# Source.net
KiCad netlist of a schematic drawn in EasyEDA Pro
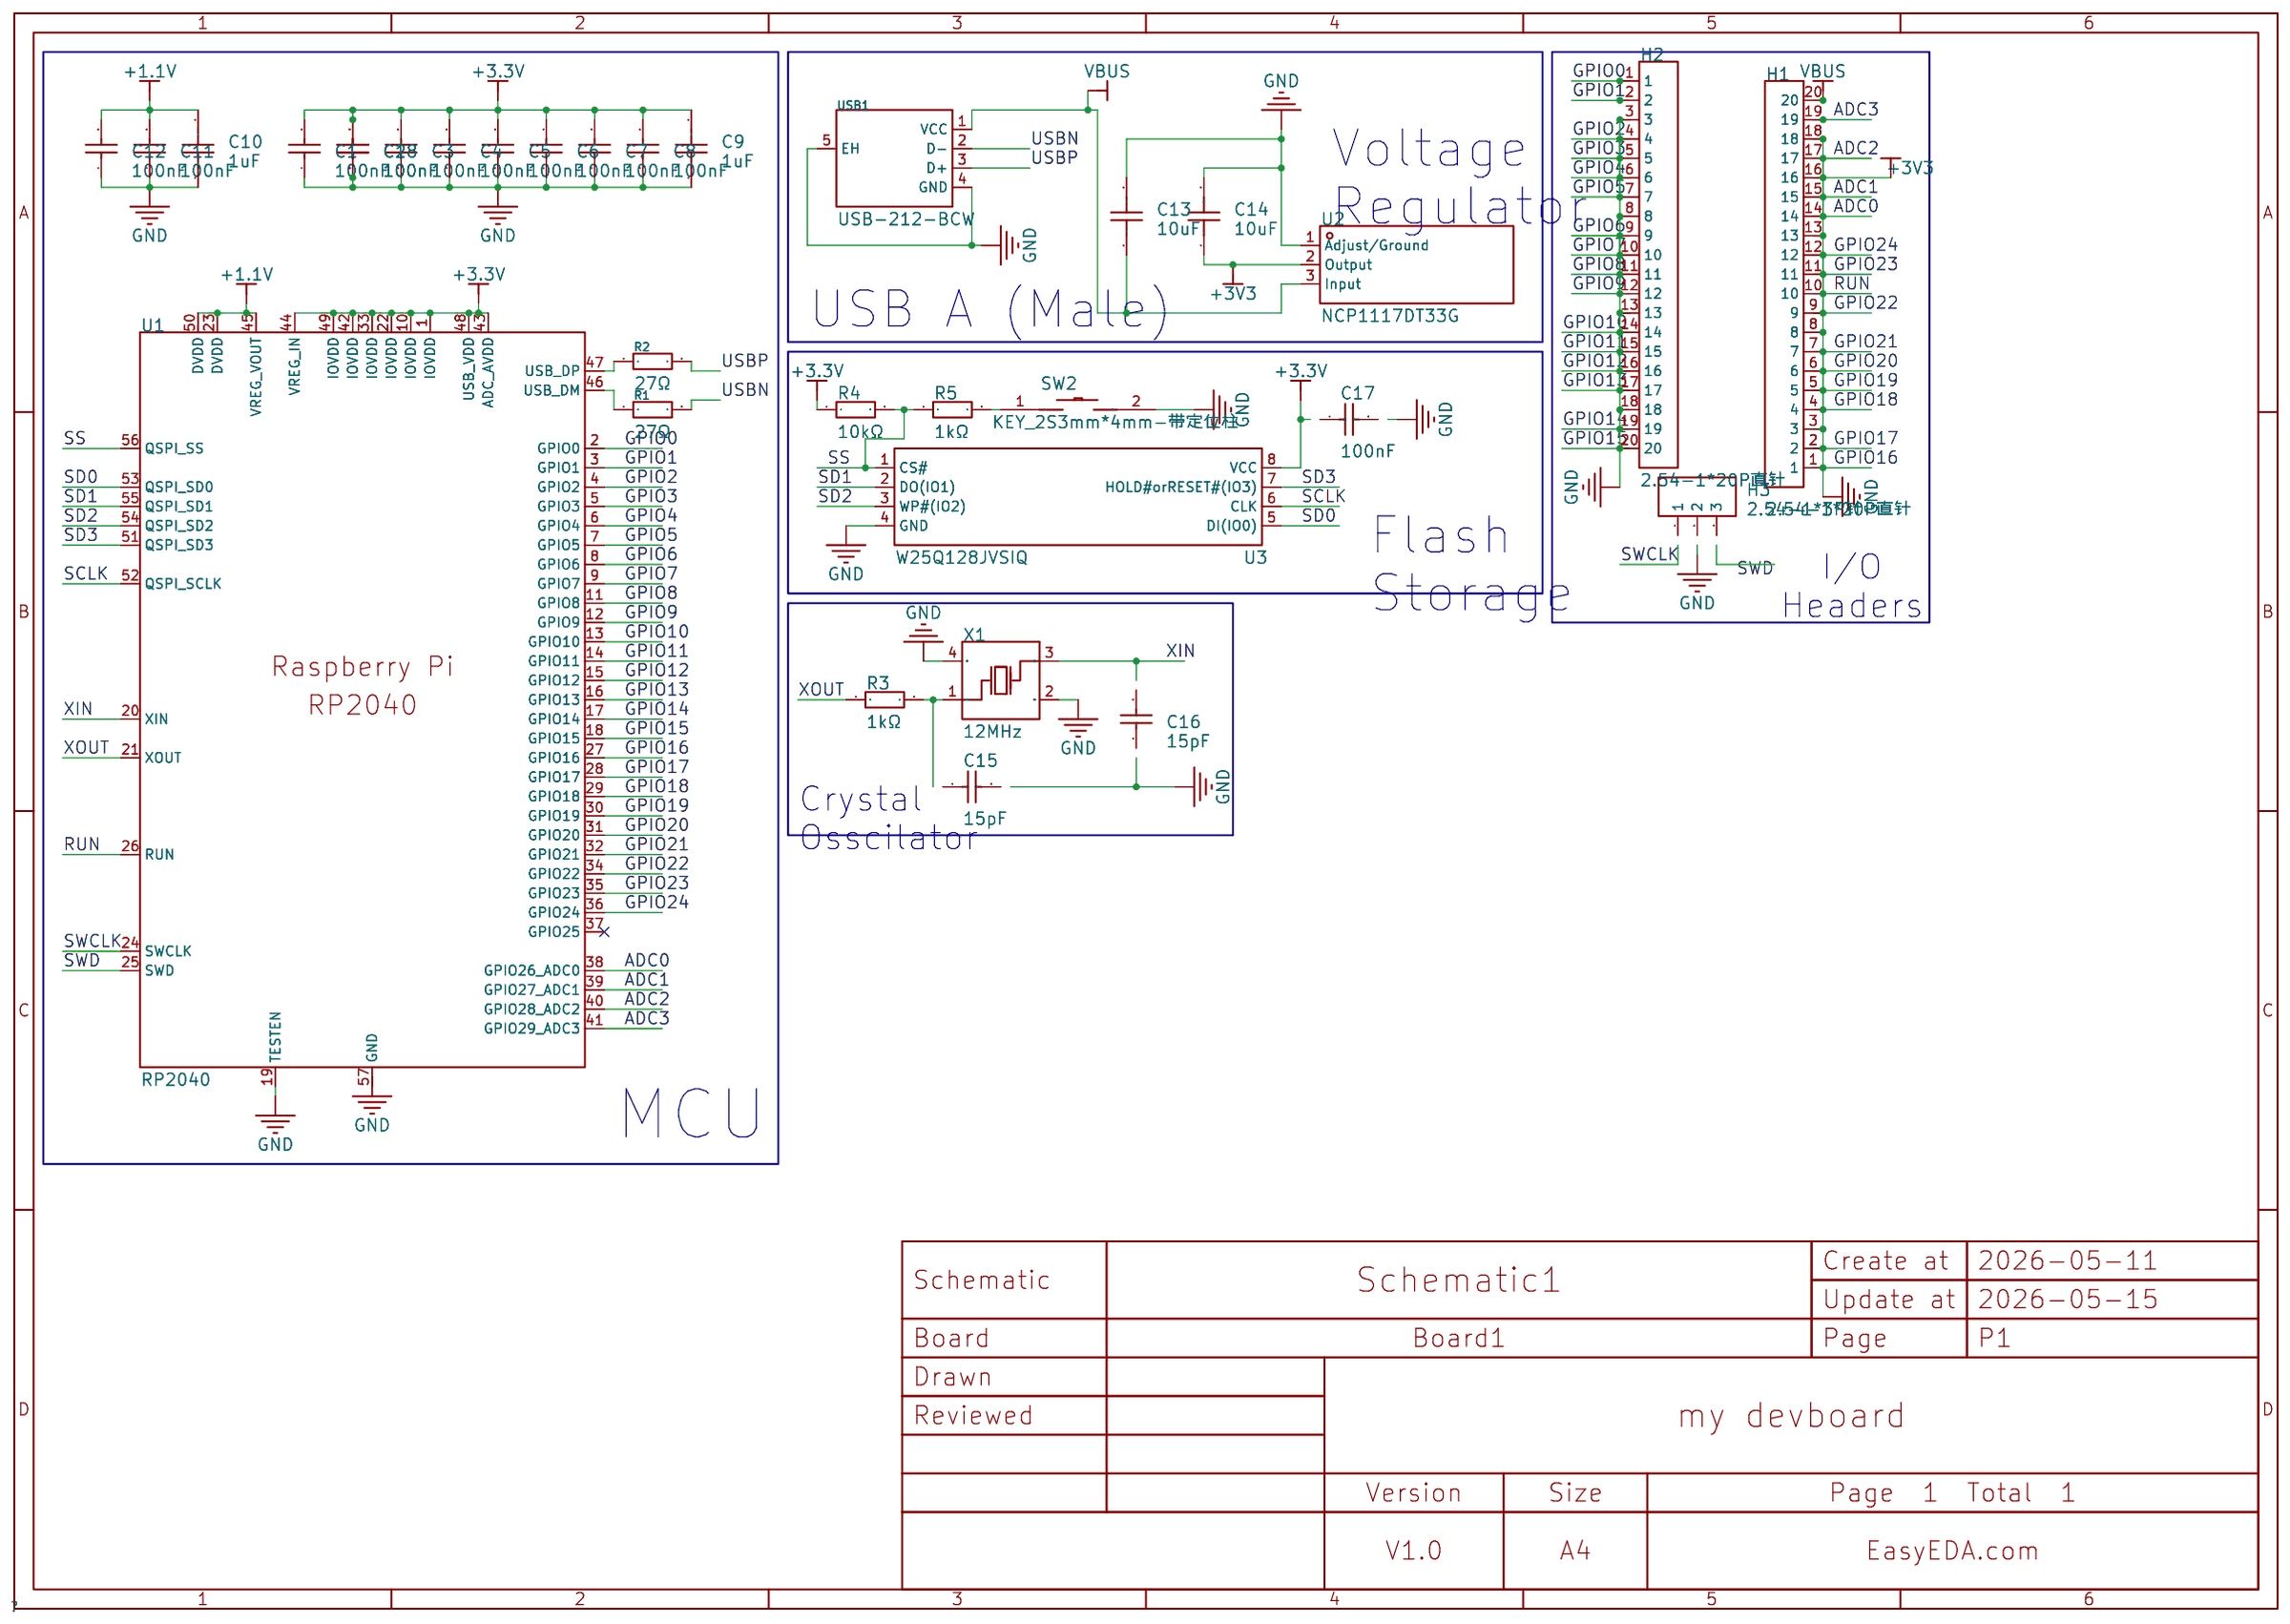
[diagram p0: schematic sheet]

(export (version "E")
  (design (tool "Eeschema 10.0.6"))
  (components
    (comp (ref "C1")
      (value "100nF")
      (footprint "easyedapro:C0603")
      (description "Capacitance:100nF Tolerance:±10% Tolerance:±10% Voltage Rating:50V Temperature Coefficient:-")
      (fields
        (field (name "Manufacturer Part") "CT41G-0603-2X1-50V-0.1uF-K(N)")
        (field (name "Manufacturer") "TORCH(火炬)")
      )
      (libsource (lib "easyedapro") (part "CT41G-0603-2X1-50V-0.1μF-K(N)"))
    )
    (comp (ref "C2")
      (value "100nF")
      (footprint "easyedapro:C0603")
      (description "Capacitance:100nF Tolerance:±10% Tolerance:±10% Voltage Rating:50V Temperature Coefficient:-")
      (fields
        (field (name "Manufacturer Part") "CT41G-0603-2X1-50V-0.1uF-K(N)")
        (field (name "Manufacturer") "TORCH(火炬)")
      )
      (libsource (lib "easyedapro") (part "CT41G-0603-2X1-50V-0.1μF-K(N)"))
    )
    (comp (ref "C3")
      (value "100nF")
      (footprint "easyedapro:C0603")
      (description "Capacitance:100nF Tolerance:±10% Tolerance:±10% Voltage Rating:50V Temperature Coefficient:-")
      (fields
        (field (name "Manufacturer Part") "CT41G-0603-2X1-50V-0.1uF-K(N)")
        (field (name "Manufacturer") "TORCH(火炬)")
      )
      (libsource (lib "easyedapro") (part "CT41G-0603-2X1-50V-0.1μF-K(N)"))
    )
    (comp (ref "C4")
      (value "100nF")
      (footprint "easyedapro:C0603")
      (description "Capacitance:100nF Tolerance:±10% Tolerance:±10% Voltage Rating:50V Temperature Coefficient:-")
      (fields
        (field (name "Manufacturer Part") "CT41G-0603-2X1-50V-0.1uF-K(N)")
        (field (name "Manufacturer") "TORCH(火炬)")
      )
      (libsource (lib "easyedapro") (part "CT41G-0603-2X1-50V-0.1μF-K(N)"))
    )
    (comp (ref "C5")
      (value "100nF")
      (footprint "easyedapro:C0603")
      (description "Capacitance:100nF Tolerance:±10% Tolerance:±10% Voltage Rating:50V Temperature Coefficient:-")
      (fields
        (field (name "Manufacturer Part") "CT41G-0603-2X1-50V-0.1uF-K(N)")
        (field (name "Manufacturer") "TORCH(火炬)")
      )
      (libsource (lib "easyedapro") (part "CT41G-0603-2X1-50V-0.1μF-K(N)"))
    )
    (comp (ref "C6")
      (value "100nF")
      (footprint "easyedapro:C0603")
      (description "Capacitance:100nF Tolerance:±10% Tolerance:±10% Voltage Rating:50V Temperature Coefficient:-")
      (fields
        (field (name "Manufacturer Part") "CT41G-0603-2X1-50V-0.1uF-K(N)")
        (field (name "Manufacturer") "TORCH(火炬)")
      )
      (libsource (lib "easyedapro") (part "CT41G-0603-2X1-50V-0.1μF-K(N)"))
    )
    (comp (ref "C7")
      (value "100nF")
      (footprint "easyedapro:C0603")
      (description "Capacitance:100nF Tolerance:±10% Tolerance:±10% Voltage Rating:50V Temperature Coefficient:-")
      (fields
        (field (name "Manufacturer Part") "CT41G-0603-2X1-50V-0.1uF-K(N)")
        (field (name "Manufacturer") "TORCH(火炬)")
      )
      (libsource (lib "easyedapro") (part "CT41G-0603-2X1-50V-0.1μF-K(N)"))
    )
    (comp (ref "C8")
      (value "100nF")
      (footprint "easyedapro:C0603")
      (description "Capacitance:100nF Tolerance:±10% Tolerance:±10% Voltage Rating:50V Temperature Coefficient:-")
      (fields
        (field (name "Manufacturer Part") "CT41G-0603-2X1-50V-0.1uF-K(N)")
        (field (name "Manufacturer") "TORCH(火炬)")
      )
      (libsource (lib "easyedapro") (part "CT41G-0603-2X1-50V-0.1μF-K(N)"))
    )
    (comp (ref "C9")
      (value "1uF")
      (footprint "easyedapro:C0603")
      (description "Capacitance:1uF Tolerance:±10% Tolerance:±10% Voltage Rating:50V Temperature Coefficient:X5R")
      (fields
        (field (name "Manufacturer Part") "CL10A105KB8NNNC")
        (field (name "Manufacturer") "SAMSUNG(三星)")
      )
      (libsource (lib "easyedapro") (part "CL10A105KB8NNNC"))
    )
    (comp (ref "C10")
      (value "1uF")
      (footprint "easyedapro:C0603")
      (description "Capacitance:1uF Tolerance:±10% Tolerance:±10% Voltage Rating:50V Temperature Coefficient:X5R")
      (fields
        (field (name "Manufacturer Part") "CL10A105KB8NNNC")
        (field (name "Manufacturer") "SAMSUNG(三星)")
      )
      (libsource (lib "easyedapro") (part "CL10A105KB8NNNC"))
    )
    (comp (ref "C11")
      (value "100nF")
      (footprint "easyedapro:C0603")
      (description "Capacitance:100nF Tolerance:±10% Tolerance:±10% Voltage Rating:50V Temperature Coefficient:-")
      (fields
        (field (name "Manufacturer Part") "CT41G-0603-2X1-50V-0.1uF-K(N)")
        (field (name "Manufacturer") "TORCH(火炬)")
      )
      (libsource (lib "easyedapro") (part "CT41G-0603-2X1-50V-0.1μF-K(N)"))
    )
    (comp (ref "C12")
      (value "100nF")
      (footprint "easyedapro:C0603")
      (description "Capacitance:100nF Tolerance:±10% Tolerance:±10% Voltage Rating:50V Temperature Coefficient:-")
      (fields
        (field (name "Manufacturer Part") "CT41G-0603-2X1-50V-0.1uF-K(N)")
        (field (name "Manufacturer") "TORCH(火炬)")
      )
      (libsource (lib "easyedapro") (part "CT41G-0603-2X1-50V-0.1μF-K(N)"))
    )
    (comp (ref "C13")
      (value "10uF")
      (footprint "easyedapro:C0603")
      (description "Capacitance:10uF Tolerance:±20% Tolerance:±20% Voltage Rating:25V Temperature Coefficient:X5R")
      (fields
        (field (name "Manufacturer Part") "CL10A106MA8NRNC")
        (field (name "Manufacturer") "SAMSUNG(三星)")
      )
      (libsource (lib "easyedapro") (part "CL10A106MA8NRNC"))
    )
    (comp (ref "C14")
      (value "10uF")
      (footprint "easyedapro:C0603")
      (description "Capacitance:10uF Tolerance:±20% Tolerance:±20% Voltage Rating:25V Temperature Coefficient:X5R")
      (fields
        (field (name "Manufacturer Part") "CL10A106MA8NRNC")
        (field (name "Manufacturer") "SAMSUNG(三星)")
      )
      (libsource (lib "easyedapro") (part "CL10A106MA8NRNC"))
    )
    (comp (ref "C15")
      (value "15pF")
      (footprint "easyedapro:C0603")
      (description "Capacitance:15pF Tolerance:±5% Tolerance:±5% Voltage Rating:50V Temperature Coefficient:C0G")
      (fields
        (field (name "Manufacturer Part") "CL10C150JB8NNNC")
        (field (name "Manufacturer") "SAMSUNG(三星)")
      )
      (libsource (lib "easyedapro") (part "CL10C150JB8NNNC"))
    )
    (comp (ref "C16")
      (value "15pF")
      (footprint "easyedapro:C0603")
      (description "Capacitance:15pF Tolerance:±5% Tolerance:±5% Voltage Rating:50V Temperature Coefficient:C0G")
      (fields
        (field (name "Manufacturer Part") "CL10C150JB8NNNC")
        (field (name "Manufacturer") "SAMSUNG(三星)")
      )
      (libsource (lib "easyedapro") (part "CL10C150JB8NNNC"))
    )
    (comp (ref "C17")
      (value "100nF")
      (footprint "easyedapro:C0603")
      (description "Capacitance:100nF Tolerance:±10% Tolerance:±10% Voltage Rating:50V Temperature Coefficient:-")
      (fields
        (field (name "Manufacturer Part") "CT41G-0603-2X1-50V-0.1uF-K(N)")
        (field (name "Manufacturer") "TORCH(火炬)")
      )
      (libsource (lib "easyedapro") (part "CT41G-0603-2X1-50V-0.1μF-K(N)"))
    )
    (comp (ref "C18")
      (value "100nF")
      (footprint "easyedapro:C0603")
      (description "Capacitance:100nF Tolerance:±10% Tolerance:±10% Voltage Rating:50V Temperature Coefficient:-")
      (fields
        (field (name "Manufacturer Part") "CT41G-0603-2X1-50V-0.1uF-K(N)")
        (field (name "Manufacturer") "TORCH(火炬)")
      )
      (libsource (lib "easyedapro") (part "CT41G-0603-2X1-50V-0.1μF-K(N)"))
    )
    (comp (ref "H1")
      (value "2.54-1*20P直针")
      (footprint "easyedapro:HDR-TH_20P-P2.54-V-M-1")
      (fields (field (name "Manufacturer") "BOOMELE(博穆精密)"))
      (libsource (lib "easyedapro") (part "Header-Male-2.54_1x20"))
    )
    (comp (ref "H2")
      (value "2.54-1*20P直针")
      (footprint "easyedapro:HDR-TH_20P-P2.54-V-M-1")
      (fields (field (name "Manufacturer") "BOOMELE(博穆精密)"))
      (libsource (lib "easyedapro") (part "Header-Male-2.54_1x20"))
    )
    (comp (ref "H3")
      (value "2.54-1*3P针")
      (footprint "easyedapro:HDR-TH_3P-P2.54-V-M-1")
      (fields (field (name "Manufacturer") "BOOMELE(博穆精密)"))
      (libsource (lib "easyedapro") (part "Header-Male-2.54_1x3"))
    )
    (comp (ref "R1")
      (value "27Ω")
      (footprint "easyedapro:R0603")
      (fields
        (field (name "Manufacturer Part") "CR0603JA0270G")
        (field (name "Manufacturer") "LIZ(丽智电子)")
        (field (name "Tolerance") "±5%")
      )
      (libsource (lib "easyedapro") (part "CR0603JA0270G"))
    )
    (comp (ref "R2")
      (value "27Ω")
      (footprint "easyedapro:R0603")
      (fields
        (field (name "Manufacturer Part") "CR0603JA0270G")
        (field (name "Manufacturer") "LIZ(丽智电子)")
        (field (name "Tolerance") "±5%")
      )
      (libsource (lib "easyedapro") (part "CR0603JA0270G"))
    )
    (comp (ref "R3")
      (value "1kΩ")
      (footprint "easyedapro:R0603")
      (fields
        (field (name "Manufacturer Part") "RC0603FR-071KL")
        (field (name "Manufacturer") "YAGEO(国巨)")
        (field (name "Tolerance") "±1%")
      )
      (libsource (lib "easyedapro") (part "RC0603FR-071KL"))
    )
    (comp (ref "R4")
      (value "10kΩ")
      (footprint "easyedapro:R0603")
      (fields
        (field (name "Manufacturer Part") "RC0603FR-0710KL")
        (field (name "Manufacturer") "YAGEO(国巨)")
        (field (name "Tolerance") "±1%")
      )
      (libsource (lib "easyedapro") (part "RC0603FR-0710KL"))
    )
    (comp (ref "R5")
      (value "1kΩ")
      (footprint "easyedapro:R0603")
      (fields
        (field (name "Manufacturer Part") "RC0603FR-071KL")
        (field (name "Manufacturer") "YAGEO(国巨)")
        (field (name "Tolerance") "±1%")
      )
      (libsource (lib "easyedapro") (part "RC0603FR-071KL"))
    )
    (comp (ref "SW2")
      (value "KEY_2S3mm*4mm-带定位柱")
      (footprint "easyedapro:KEY-SMD_L4.0-W3.7-LS4.8")
      (libsource (lib "easyedapro") (part "KEY_2S3MM*4MM-带定位柱"))
    )
    (comp (ref "U1")
      (value "RP2040")
      (footprint "easyedapro:QFN-56_L7.0-W7.0-P0.40-TL-EP4.0")
      (fields (field (name "Manufacturer") "Raspberry Pi(树莓派)"))
      (libsource (lib "easyedapro") (part "RP2040_C2961140"))
    )
    (comp (ref "U2")
      (value "NCP1117DT33G")
      (footprint "easyedapro:TO-252_L6.5-W6.1-P4.58-LS9.9-BR")
      (fields (field (name "Manufacturer") "onsemi(安森美)"))
      (libsource (lib "easyedapro") (part "NCP1117DT33G"))
    )
    (comp (ref "U3")
      (value "W25Q128JVSIQ")
      (footprint "easyedapro:SOIC-8_L5.3-W5.3-P1.27-LS8.0-BL")
      (fields (field (name "Manufacturer") "Winbond(华邦)"))
      (libsource (lib "easyedapro") (part "W25Q128JVSIQ"))
    )
    (comp (ref "USB1")
      (value "USB-212-BCW")
      (footprint "easyedapro:USB-A-SMD_USB-212-BCW")
      (fields (field (name "Manufacturer") "XUNPU(讯普)"))
      (libsource (lib "easyedapro") (part "USB-212-BCW"))
    )
    (comp (ref "X1")
      (value "12MHz")
      (footprint "easyedapro:CRYSTAL-SMD_4P-L3.2-W2.5-BL")
      (fields (field (name "Manufacturer Part") "X322512MSB4SI") (field (name "Manufacturer") "YXC(扬兴晶振)"))
      (libsource (lib "easyedapro") (part "X322512MSB4SI"))
    )
  )
  (nets
    (net (code "1") (name "+1.1V") (class "Default")
      (node (ref "C10") (pin "2") (pinfunction "2_2") (pintype "unspecified"))
      (node (ref "C11") (pin "2") (pinfunction "2_2") (pintype "input"))
      (node (ref "C12") (pin "2") (pinfunction "2_2") (pintype "input"))
      (node (ref "U1") (pin "23") (pinfunction "DVDD_23") (pintype "bidirectional"))
      (node (ref "U1") (pin "45") (pinfunction "VREG_VOUT_45") (pintype "bidirectional"))
      (node (ref "U1") (pin "50") (pinfunction "DVDD_50") (pintype "bidirectional"))
    )
    (net (code "2") (name "+3.3V") (class "Default")
      (node (ref "C1") (pin "2") (pinfunction "2_2") (pintype "input"))
      (node (ref "C18") (pin "2") (pinfunction "2_2") (pintype "input"))
      (node (ref "C2") (pin "2") (pinfunction "2_2") (pintype "input"))
      (node (ref "C3") (pin "2") (pinfunction "2_2") (pintype "input"))
      (node (ref "C4") (pin "2") (pinfunction "2_2") (pintype "input"))
      (node (ref "C5") (pin "2") (pinfunction "2_2") (pintype "input"))
      (node (ref "C6") (pin "2") (pinfunction "2_2") (pintype "input"))
      (node (ref "C7") (pin "2") (pinfunction "2_2") (pintype "input"))
      (node (ref "C8") (pin "2") (pinfunction "2_2") (pintype "input"))
      (node (ref "C9") (pin "2") (pinfunction "2_2") (pintype "unspecified"))
      (node (ref "R4") (pin "1") (pinfunction "1_1") (pintype "input"))
      (node (ref "U1") (pin "1") (pinfunction "IOVDD_1") (pintype "bidirectional"))
      (node (ref "U1") (pin "10") (pinfunction "IOVDD_10") (pintype "bidirectional"))
      (node (ref "U1") (pin "22") (pinfunction "IOVDD_22") (pintype "bidirectional"))
      (node (ref "U1") (pin "33") (pinfunction "IOVDD_33") (pintype "bidirectional"))
      (node (ref "U1") (pin "42") (pinfunction "IOVDD_42") (pintype "bidirectional"))
      (node (ref "U1") (pin "43") (pinfunction "ADC_AVDD_43") (pintype "bidirectional"))
      (node (ref "U1") (pin "44") (pinfunction "VREG_IN_44") (pintype "bidirectional"))
      (node (ref "U1") (pin "48") (pinfunction "USB_VDD_48") (pintype "bidirectional"))
      (node (ref "U1") (pin "49") (pinfunction "IOVDD_49") (pintype "bidirectional"))
      (node (ref "U3") (pin "8") (pinfunction "VCC_8") (pintype "unspecified"))
    )
    (net (code "3") (name "+3V3") (class "Default")
      (node (ref "C1") (pin "1") (pinfunction "1_1") (pintype "input"))
      (node (ref "C10") (pin "1") (pinfunction "1_1") (pintype "unspecified"))
      (node (ref "C11") (pin "1") (pinfunction "1_1") (pintype "input"))
      (node (ref "C12") (pin "1") (pinfunction "1_1") (pintype "input"))
      (node (ref "C13") (pin "2") (pinfunction "2_2") (pintype "input"))
      (node (ref "C14") (pin "1") (pinfunction "1_1") (pintype "input"))
      (node (ref "C14") (pin "2") (pinfunction "2_2") (pintype "input"))
      (node (ref "C18") (pin "1") (pinfunction "1_1") (pintype "input"))
      (node (ref "C2") (pin "1") (pinfunction "1_1") (pintype "input"))
      (node (ref "C3") (pin "1") (pinfunction "1_1") (pintype "input"))
      (node (ref "C4") (pin "1") (pinfunction "1_1") (pintype "input"))
      (node (ref "C5") (pin "1") (pinfunction "1_1") (pintype "input"))
      (node (ref "C6") (pin "1") (pinfunction "1_1") (pintype "input"))
      (node (ref "C7") (pin "1") (pinfunction "1_1") (pintype "input"))
      (node (ref "C8") (pin "1") (pinfunction "1_1") (pintype "input"))
      (node (ref "C9") (pin "1") (pinfunction "1_1") (pintype "unspecified"))
      (node (ref "H1") (pin "1") (pinfunction "1_1") (pintype "unspecified"))
      (node (ref "H1") (pin "10") (pinfunction "10_10") (pintype "unspecified"))
      (node (ref "H1") (pin "11") (pinfunction "11_11") (pintype "unspecified"))
      (node (ref "H1") (pin "12") (pinfunction "12_12") (pintype "unspecified"))
      (node (ref "H1") (pin "13") (pinfunction "13_13") (pintype "unspecified"))
      (node (ref "H1") (pin "14") (pinfunction "14_14") (pintype "unspecified"))
      (node (ref "H1") (pin "15") (pinfunction "15_15") (pintype "unspecified"))
      (node (ref "H1") (pin "16") (pinfunction "16_16") (pintype "unspecified"))
      (node (ref "H1") (pin "17") (pinfunction "17_17") (pintype "unspecified"))
      (node (ref "H1") (pin "18") (pinfunction "18_18") (pintype "unspecified"))
      (node (ref "H1") (pin "2") (pinfunction "2_2") (pintype "unspecified"))
      (node (ref "H1") (pin "3") (pinfunction "3_3") (pintype "unspecified"))
      (node (ref "H1") (pin "4") (pinfunction "4_4") (pintype "unspecified"))
      (node (ref "H1") (pin "5") (pinfunction "5_5") (pintype "unspecified"))
      (node (ref "H1") (pin "6") (pinfunction "6_6") (pintype "unspecified"))
      (node (ref "H1") (pin "7") (pinfunction "7_7") (pintype "unspecified"))
      (node (ref "H1") (pin "8") (pinfunction "8_8") (pintype "unspecified"))
      (node (ref "H1") (pin "9") (pinfunction "9_9") (pintype "unspecified"))
      (node (ref "H2") (pin "10") (pinfunction "10_10") (pintype "unspecified"))
      (node (ref "H2") (pin "11") (pinfunction "11_11") (pintype "unspecified"))
      (node (ref "H2") (pin "12") (pinfunction "12_12") (pintype "unspecified"))
      (node (ref "H2") (pin "13") (pinfunction "13_13") (pintype "unspecified"))
      (node (ref "H2") (pin "14") (pinfunction "14_14") (pintype "unspecified"))
      (node (ref "H2") (pin "15") (pinfunction "15_15") (pintype "unspecified"))
      (node (ref "H2") (pin "16") (pinfunction "16_16") (pintype "unspecified"))
      (node (ref "H2") (pin "17") (pinfunction "17_17") (pintype "unspecified"))
      (node (ref "H2") (pin "18") (pinfunction "18_18") (pintype "unspecified"))
      (node (ref "H2") (pin "19") (pinfunction "19_19") (pintype "unspecified"))
      (node (ref "H2") (pin "20") (pinfunction "20_20") (pintype "unspecified"))
      (node (ref "H2") (pin "3") (pinfunction "3_3") (pintype "unspecified"))
      (node (ref "H2") (pin "4") (pinfunction "4_4") (pintype "unspecified"))
      (node (ref "H2") (pin "5") (pinfunction "5_5") (pintype "unspecified"))
      (node (ref "H2") (pin "6") (pinfunction "6_6") (pintype "unspecified"))
      (node (ref "H2") (pin "7") (pinfunction "7_7") (pintype "unspecified"))
      (node (ref "H2") (pin "8") (pinfunction "8_8") (pintype "unspecified"))
      (node (ref "H2") (pin "9") (pinfunction "9_9") (pintype "unspecified"))
      (node (ref "SW2") (pin "2") (pinfunction "2_2") (pintype "unspecified"))
      (node (ref "U1") (pin "11") (pinfunction "GPIO8_11") (pintype "bidirectional"))
      (node (ref "U1") (pin "12") (pinfunction "GPIO9_12") (pintype "bidirectional"))
      (node (ref "U1") (pin "13") (pinfunction "GPIO10_13") (pintype "bidirectional"))
      (node (ref "U1") (pin "14") (pinfunction "GPIO11_14") (pintype "bidirectional"))
      (node (ref "U1") (pin "15") (pinfunction "GPIO12_15") (pintype "bidirectional"))
      (node (ref "U1") (pin "16") (pinfunction "GPIO13_16") (pintype "bidirectional"))
      (node (ref "U1") (pin "17") (pinfunction "GPIO14_17") (pintype "bidirectional"))
      (node (ref "U1") (pin "18") (pinfunction "GPIO15_18") (pintype "bidirectional"))
      (node (ref "U1") (pin "19") (pinfunction "TESTEN_19") (pintype "unspecified"))
      (node (ref "U1") (pin "26") (pinfunction "RUN_26") (pintype "input"))
      (node (ref "U1") (pin "27") (pinfunction "GPIO16_27") (pintype "bidirectional"))
      (node (ref "U1") (pin "28") (pinfunction "GPIO17_28") (pintype "bidirectional"))
      (node (ref "U1") (pin "29") (pinfunction "GPIO18_29") (pintype "bidirectional"))
      (node (ref "U1") (pin "30") (pinfunction "GPIO19_30") (pintype "bidirectional"))
      (node (ref "U1") (pin "31") (pinfunction "GPIO20_31") (pintype "bidirectional"))
      (node (ref "U1") (pin "32") (pinfunction "GPIO21_32") (pintype "bidirectional"))
      (node (ref "U1") (pin "34") (pinfunction "GPIO22_34") (pintype "bidirectional"))
      (node (ref "U1") (pin "35") (pinfunction "GPIO23_35") (pintype "bidirectional"))
      (node (ref "U1") (pin "36") (pinfunction "GPIO24_36") (pintype "bidirectional"))
      (node (ref "U1") (pin "38") (pinfunction "GPIO26_ADC0_38") (pintype "bidirectional"))
      (node (ref "U1") (pin "39") (pinfunction "GPIO27_ADC1_39") (pintype "bidirectional"))
      (node (ref "U1") (pin "4") (pinfunction "GPIO2_4") (pintype "bidirectional"))
      (node (ref "U1") (pin "40") (pinfunction "GPIO28_ADC2_40") (pintype "bidirectional"))
      (node (ref "U1") (pin "5") (pinfunction "GPIO3_5") (pintype "bidirectional"))
      (node (ref "U1") (pin "57") (pinfunction "GND_57") (pintype "bidirectional"))
      (node (ref "U1") (pin "6") (pinfunction "GPIO4_6") (pintype "bidirectional"))
      (node (ref "U1") (pin "7") (pinfunction "GPIO5_7") (pintype "bidirectional"))
      (node (ref "U1") (pin "8") (pinfunction "GPIO6_8") (pintype "bidirectional"))
      (node (ref "U1") (pin "9") (pinfunction "GPIO7_9") (pintype "bidirectional"))
      (node (ref "U2") (pin "1") (pinfunction "Adjust/Ground_1") (pintype "unspecified"))
      (node (ref "U2") (pin "2") (pinfunction "Output_2") (pintype "unspecified"))
      (node (ref "U3") (pin "4") (pinfunction "GND_4") (pintype "unspecified"))
      (node (ref "USB1") (pin "4") (pinfunction "GND_4") (pintype "input"))
      (node (ref "USB1") (pin "5") (pinfunction "EH_5") (pintype "input"))
      (node (ref "X1") (pin "2") (pinfunction "GND_2") (pintype "unspecified"))
      (node (ref "X1") (pin "4") (pinfunction "GND_4") (pintype "unspecified"))
    )
    (net (code "4") (name "/ADC3") (class "Default")
      (node (ref "H1") (pin "19") (pinfunction "19_19") (pintype "unspecified"))
      (node (ref "U1") (pin "41") (pinfunction "GPIO29_ADC3_41") (pintype "bidirectional"))
    )
    (net (code "5") (name "/GPIO0") (class "Default")
      (node (ref "H2") (pin "1") (pinfunction "1_1") (pintype "unspecified"))
      (node (ref "U1") (pin "2") (pinfunction "GPIO0_2") (pintype "bidirectional"))
    )
    (net (code "6") (name "/GPIO1") (class "Default")
      (node (ref "H2") (pin "2") (pinfunction "2_2") (pintype "unspecified"))
      (node (ref "U1") (pin "3") (pinfunction "GPIO1_3") (pintype "bidirectional"))
    )
    (net (code "7") (name "/SCLK") (class "Default")
      (node (ref "U1") (pin "52") (pinfunction "QSPI_SCLK_52") (pintype "output"))
      (node (ref "U3") (pin "6") (pinfunction "CLK_6") (pintype "unspecified"))
    )
    (net (code "8") (name "/SD0") (class "Default")
      (node (ref "U1") (pin "53") (pinfunction "QSPI_SD0_53") (pintype "bidirectional"))
      (node (ref "U3") (pin "5") (pinfunction "DI(IO0)_5") (pintype "unspecified"))
    )
    (net (code "9") (name "/SD1") (class "Default")
      (node (ref "U1") (pin "55") (pinfunction "QSPI_SD1_55") (pintype "bidirectional"))
      (node (ref "U3") (pin "2") (pinfunction "DO(IO1)_2") (pintype "unspecified"))
    )
    (net (code "10") (name "/SD2") (class "Default")
      (node (ref "U1") (pin "54") (pinfunction "QSPI_SD2_54") (pintype "bidirectional"))
      (node (ref "U3") (pin "3") (pinfunction "WP#(IO2)_3") (pintype "unspecified"))
    )
    (net (code "11") (name "/SD3") (class "Default")
      (node (ref "U1") (pin "51") (pinfunction "QSPI_SD3_51") (pintype "bidirectional"))
      (node (ref "U3") (pin "7") (pinfunction "HOLD#orRESET#(IO3)_7") (pintype "unspecified"))
    )
    (net (code "12") (name "/SS") (class "Default")
      (node (ref "R4") (pin "2") (pinfunction "2_2") (pintype "input"))
      (node (ref "R5") (pin "1") (pinfunction "1_1") (pintype "input"))
      (node (ref "U1") (pin "56") (pinfunction "QSPI_SS_56") (pintype "bidirectional"))
      (node (ref "U3") (pin "1") (pinfunction "CS#_1") (pintype "unspecified"))
    )
    (net (code "13") (name "/SWCLK") (class "Default")
      (node (ref "U1") (pin "24") (pinfunction "SWCLK_24") (pintype "output"))
    )
    (net (code "14") (name "/SWD") (class "Default")
      (node (ref "U1") (pin "25") (pinfunction "SWD_25") (pintype "bidirectional"))
    )
    (net (code "15") (name "/USBN") (class "Default")
      (node (ref "R1") (pin "2") (pinfunction "2_2") (pintype "input"))
      (node (ref "USB1") (pin "2") (pinfunction "D-_2") (pintype "input"))
    )
    (net (code "16") (name "/USBP") (class "Default")
      (node (ref "R2") (pin "2") (pinfunction "2_2") (pintype "input"))
      (node (ref "USB1") (pin "3") (pinfunction "D+_3") (pintype "input"))
    )
    (net (code "17") (name "/XIN") (class "Default")
      (node (ref "U1") (pin "20") (pinfunction "XIN_20") (pintype "input"))
      (node (ref "X1") (pin "3") (pinfunction "OSC2_3") (pintype "unspecified"))
    )
    (net (code "18") (name "/XOUT") (class "Default")
      (node (ref "R3") (pin "1") (pinfunction "1_1") (pintype "input"))
      (node (ref "U1") (pin "21") (pinfunction "XOUT_21") (pintype "unspecified"))
    )
    (net (code "19") (name "Net-(R5-Pad2)") (class "Default")
      (node (ref "R5") (pin "2") (pinfunction "2_2") (pintype "input"))
      (node (ref "SW2") (pin "1") (pinfunction "1_1") (pintype "unspecified"))
    )
    (net (code "20") (name "Net-(U1-USB_DM)") (class "Default")
      (node (ref "R1") (pin "1") (pinfunction "1_1") (pintype "input"))
      (node (ref "U1") (pin "46") (pinfunction "USB_DM_46") (pintype "bidirectional"))
    )
    (net (code "21") (name "Net-(U1-USB_DP)") (class "Default")
      (node (ref "R2") (pin "1") (pinfunction "1_1") (pintype "input"))
      (node (ref "U1") (pin "47") (pinfunction "USB_DP_47") (pintype "bidirectional"))
    )
    (net (code "22") (name "Net-(X1-OSC1)") (class "Default")
      (node (ref "R3") (pin "2") (pinfunction "2_2") (pintype "input"))
      (node (ref "X1") (pin "1") (pinfunction "OSC1_1") (pintype "unspecified"))
    )
    (net (code "23") (name "VBUS") (class "Default")
      (node (ref "C13") (pin "1") (pinfunction "1_1") (pintype "input"))
      (node (ref "H1") (pin "20") (pinfunction "20_20") (pintype "unspecified"))
      (node (ref "U2") (pin "3") (pinfunction "Input_3") (pintype "unspecified"))
      (node (ref "USB1") (pin "1") (pinfunction "VCC_1") (pintype "input"))
    )
    (net (code "24") (name "unconnected-(C15-Pad1)") (class "Default")
      (node (ref "C15") (pin "1") (pinfunction "1_1") (pintype "input"))
    )
    (net (code "25") (name "unconnected-(C15-Pad2)") (class "Default")
      (node (ref "C15") (pin "2") (pinfunction "2_2") (pintype "input"))
    )
    (net (code "26") (name "unconnected-(C16-Pad1)") (class "Default")
      (node (ref "C16") (pin "1") (pinfunction "1_1") (pintype "input"))
    )
    (net (code "27") (name "unconnected-(C16-Pad2)") (class "Default")
      (node (ref "C16") (pin "2") (pinfunction "2_2") (pintype "input"))
    )
    (net (code "28") (name "unconnected-(C17-Pad1)") (class "Default")
      (node (ref "C17") (pin "1") (pinfunction "1_1") (pintype "input"))
    )
    (net (code "29") (name "unconnected-(C17-Pad2)") (class "Default")
      (node (ref "C17") (pin "2") (pinfunction "2_2") (pintype "input"))
    )
    (net (code "30") (name "unconnected-(H3-Pad1)") (class "Default")
      (node (ref "H3") (pin "1") (pinfunction "1_1") (pintype "input"))
    )
    (net (code "31") (name "unconnected-(H3-Pad2)") (class "Default")
      (node (ref "H3") (pin "2") (pinfunction "2_2") (pintype "input"))
    )
    (net (code "32") (name "unconnected-(H3-Pad3)") (class "Default")
      (node (ref "H3") (pin "3") (pinfunction "3_3") (pintype "input"))
    )
    (net (code "33") (name "unconnected-(U1-GPIO25-Pad37)") (class "Default")
      (node (ref "U1") (pin "37") (pinfunction "GPIO25_37") (pintype "bidirectional+no_connect"))
    )
  )
)
